# USB_Power_Hub.net
KiCad netlist of a schematic drawn in EAGLE
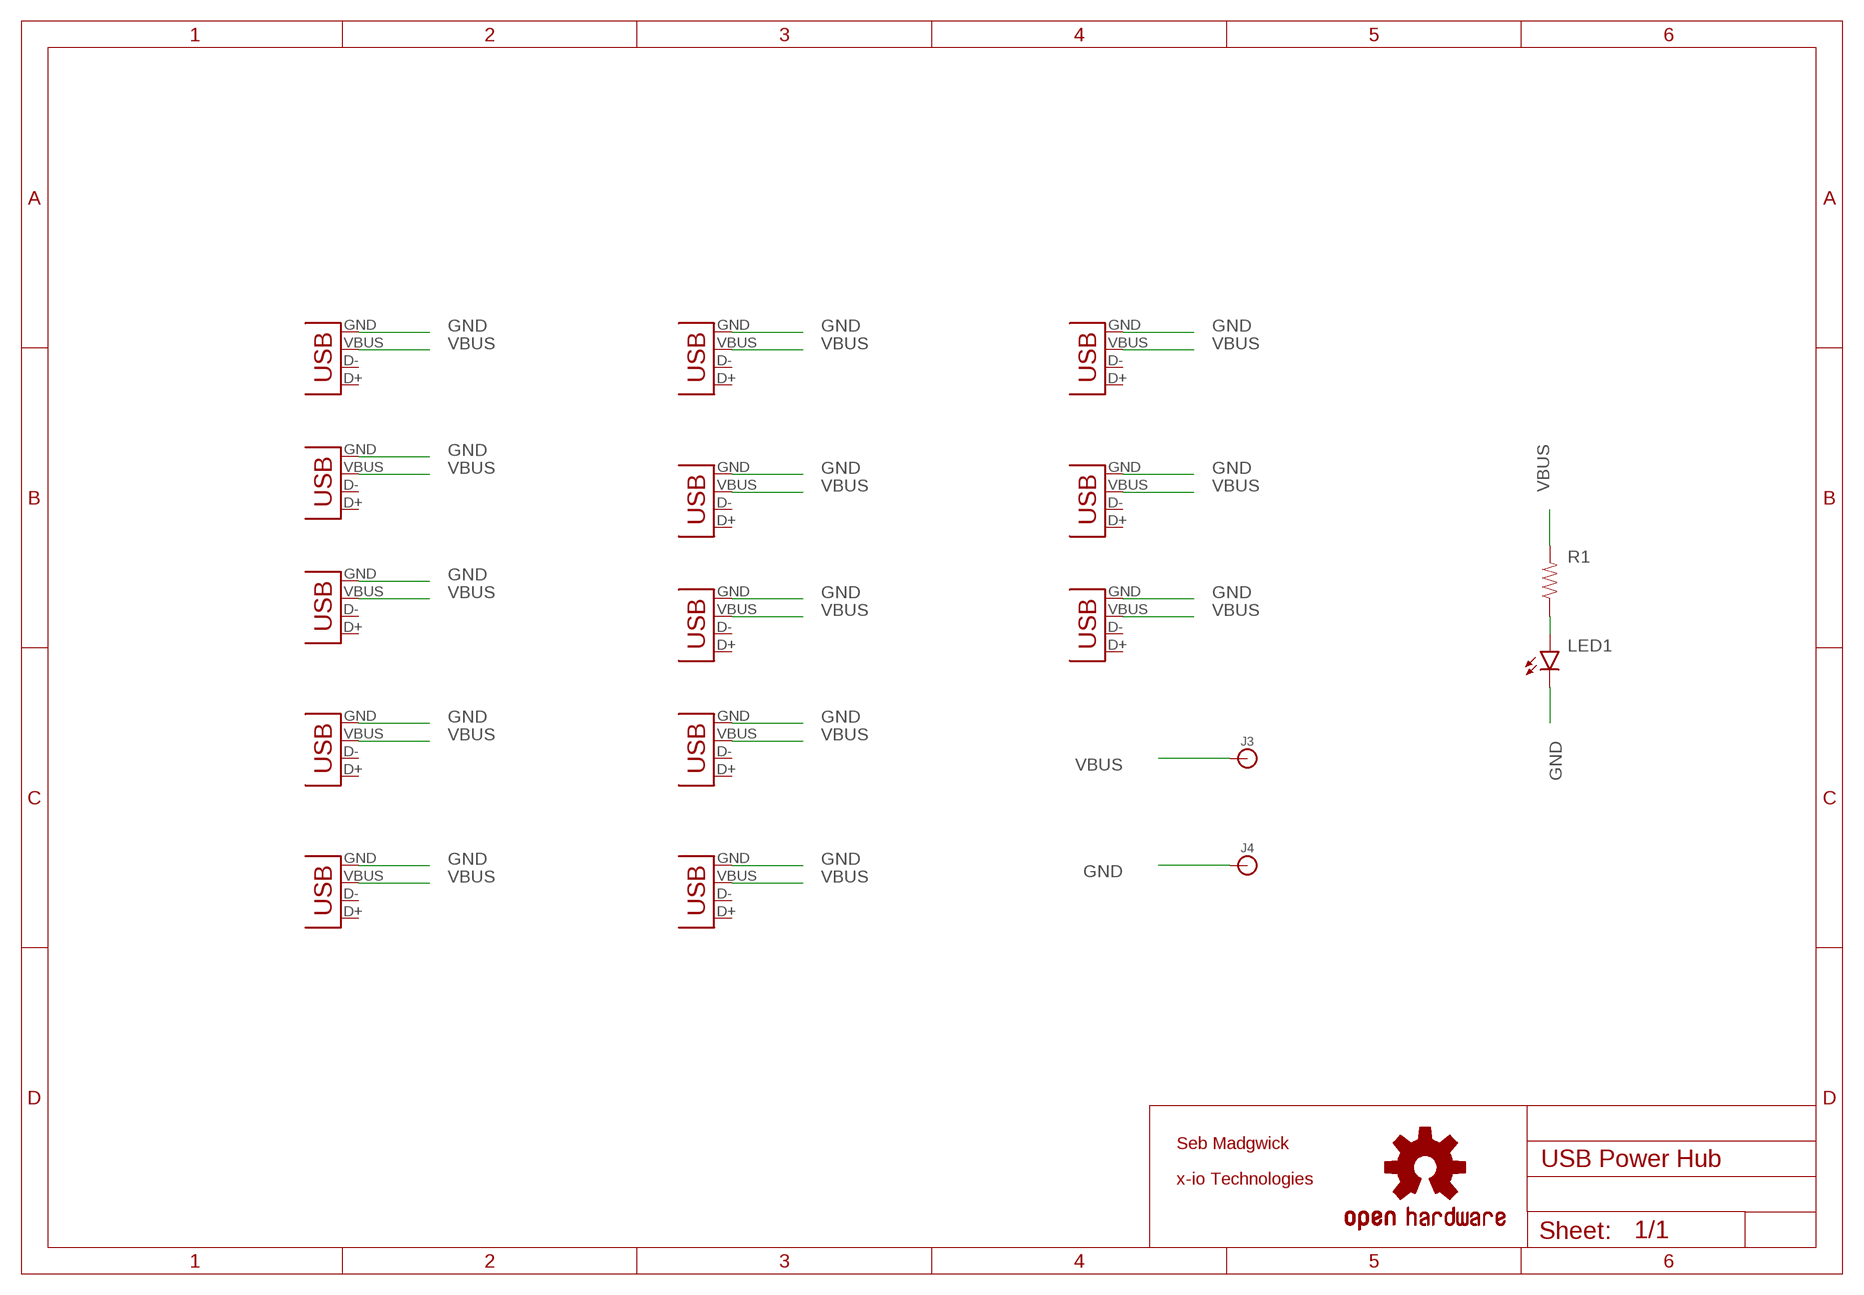
[diagram p0: schematic, sheet 1]

(export (version "E")
  (design (tool "Eeschema 10.0.6"))
  (components
    (comp (ref "J3")
      (value "BANANA_CONN")
      (footprint "eagle-import:BANANA_CONN")
      (libsource (lib "eagle-import") (part "BANANA_CONN"))
    )
    (comp (ref "J4")
      (value "BANANA_CONN")
      (footprint "eagle-import:BANANA_CONN")
      (libsource (lib "eagle-import") (part "BANANA_CONN"))
    )
    (comp (ref "JP1")
      (value "USB-A-S")
      (footprint "eagle-import:USB-A-S")
      (libsource (lib "eagle-import") (part "USB-A-S"))
    )
    (comp (ref "JP2")
      (value "USB-A-S")
      (footprint "eagle-import:USB-A-S")
      (libsource (lib "eagle-import") (part "USB-A-S"))
    )
    (comp (ref "JP3")
      (value "USB-A-S")
      (footprint "eagle-import:USB-A-S")
      (libsource (lib "eagle-import") (part "USB-A-S"))
    )
    (comp (ref "JP4")
      (value "USB-A-S")
      (footprint "eagle-import:USB-A-S")
      (libsource (lib "eagle-import") (part "USB-A-S"))
    )
    (comp (ref "JP5")
      (value "USB-A-S")
      (footprint "eagle-import:USB-A-S")
      (libsource (lib "eagle-import") (part "USB-A-S"))
    )
    (comp (ref "JP6")
      (value "USB-A-S")
      (footprint "eagle-import:USB-A-S")
      (libsource (lib "eagle-import") (part "USB-A-S"))
    )
    (comp (ref "JP7")
      (value "USB-A-S")
      (footprint "eagle-import:USB-A-S")
      (libsource (lib "eagle-import") (part "USB-A-S"))
    )
    (comp (ref "JP8")
      (value "USB-A-S")
      (footprint "eagle-import:USB-A-S")
      (libsource (lib "eagle-import") (part "USB-A-S"))
    )
    (comp (ref "JP9")
      (value "USB-A-S")
      (footprint "eagle-import:USB-A-S")
      (libsource (lib "eagle-import") (part "USB-A-S"))
    )
    (comp (ref "JP10")
      (value "USB-A-S")
      (footprint "eagle-import:USB-A-S")
      (libsource (lib "eagle-import") (part "USB-A-S"))
    )
    (comp (ref "JP11")
      (value "USB-A-S")
      (footprint "eagle-import:USB-A-S")
      (libsource (lib "eagle-import") (part "USB-A-S"))
    )
    (comp (ref "JP12")
      (value "USB-A-S")
      (footprint "eagle-import:USB-A-S")
      (libsource (lib "eagle-import") (part "USB-A-S"))
    )
    (comp (ref "JP13")
      (value "USB-A-S")
      (footprint "eagle-import:USB-A-S")
      (libsource (lib "eagle-import") (part "USB-A-S"))
    )
    (comp (ref "LED1")
      (value "LED5MM")
      (footprint "eagle-import:LED5MM")
      (libsource (lib "eagle-import") (part "LED5MM"))
    )
    (comp (ref "LOGO1")
      (value "OSHW-LOGOL")
      (footprint "eagle-import:OSHW-LOGO-L")
      (libsource (lib "eagle-import") (part "OSHW-LOGOL"))
    )
    (comp (ref "R1")
      (value "RESISTOREZ")
      (footprint "eagle-import:AXIAL-0.3EZ")
      (libsource (lib "eagle-import") (part "RESISTOREZ"))
    )
  )
  (nets
    (net (code "1") (name "/GND") (class "Default")
      (node (ref "J4") (pin "P$1") (pinfunction "1_P$1") (pintype "passive"))
      (node (ref "JP1") (pin "GND") (pinfunction "GND_GND") (pintype "bidirectional"))
      (node (ref "JP10") (pin "GND") (pinfunction "GND_GND") (pintype "bidirectional"))
      (node (ref "JP11") (pin "GND") (pinfunction "GND_GND") (pintype "bidirectional"))
      (node (ref "JP12") (pin "GND") (pinfunction "GND_GND") (pintype "bidirectional"))
      (node (ref "JP13") (pin "GND") (pinfunction "GND_GND") (pintype "bidirectional"))
      (node (ref "JP2") (pin "GND") (pinfunction "GND_GND") (pintype "bidirectional"))
      (node (ref "JP3") (pin "GND") (pinfunction "GND_GND") (pintype "bidirectional"))
      (node (ref "JP4") (pin "GND") (pinfunction "GND_GND") (pintype "bidirectional"))
      (node (ref "JP5") (pin "GND") (pinfunction "GND_GND") (pintype "bidirectional"))
      (node (ref "JP6") (pin "GND") (pinfunction "GND_GND") (pintype "bidirectional"))
      (node (ref "JP7") (pin "GND") (pinfunction "GND_GND") (pintype "bidirectional"))
      (node (ref "JP8") (pin "GND") (pinfunction "GND_GND") (pintype "bidirectional"))
      (node (ref "JP9") (pin "GND") (pinfunction "GND_GND") (pintype "bidirectional"))
      (node (ref "LED1") (pin "K") (pinfunction "C_K") (pintype "passive"))
    )
    (net (code "2") (name "/VBUS") (class "Default")
      (node (ref "J3") (pin "P$1") (pinfunction "1_P$1") (pintype "passive"))
      (node (ref "JP1") (pin "VBUS") (pinfunction "VBUS_VBUS") (pintype "bidirectional"))
      (node (ref "JP10") (pin "VBUS") (pinfunction "VBUS_VBUS") (pintype "bidirectional"))
      (node (ref "JP11") (pin "VBUS") (pinfunction "VBUS_VBUS") (pintype "bidirectional"))
      (node (ref "JP12") (pin "VBUS") (pinfunction "VBUS_VBUS") (pintype "bidirectional"))
      (node (ref "JP13") (pin "VBUS") (pinfunction "VBUS_VBUS") (pintype "bidirectional"))
      (node (ref "JP2") (pin "VBUS") (pinfunction "VBUS_VBUS") (pintype "bidirectional"))
      (node (ref "JP3") (pin "VBUS") (pinfunction "VBUS_VBUS") (pintype "bidirectional"))
      (node (ref "JP4") (pin "VBUS") (pinfunction "VBUS_VBUS") (pintype "bidirectional"))
      (node (ref "JP5") (pin "VBUS") (pinfunction "VBUS_VBUS") (pintype "bidirectional"))
      (node (ref "JP6") (pin "VBUS") (pinfunction "VBUS_VBUS") (pintype "bidirectional"))
      (node (ref "JP7") (pin "VBUS") (pinfunction "VBUS_VBUS") (pintype "bidirectional"))
      (node (ref "JP8") (pin "VBUS") (pinfunction "VBUS_VBUS") (pintype "bidirectional"))
      (node (ref "JP9") (pin "VBUS") (pinfunction "VBUS_VBUS") (pintype "bidirectional"))
      (node (ref "R1") (pin "P$2") (pinfunction "2_P$2") (pintype "passive"))
    )
    (net (code "3") (name "Net-(R1-1)") (class "Default")
      (node (ref "LED1") (pin "A") (pinfunction "A_A") (pintype "passive"))
      (node (ref "R1") (pin "P$1") (pinfunction "1_P$1") (pintype "passive"))
    )
    (net (code "4") (name "unconnected-(JP1-PadD+)") (class "Default")
      (node (ref "JP1") (pin "D+") (pinfunction "D+_D+") (pintype "bidirectional"))
    )
    (net (code "5") (name "unconnected-(JP1-PadD-)") (class "Default")
      (node (ref "JP1") (pin "D-") (pinfunction "D-_D-") (pintype "bidirectional"))
    )
    (net (code "6") (name "unconnected-(JP2-PadD+)") (class "Default")
      (node (ref "JP2") (pin "D+") (pinfunction "D+_D+") (pintype "bidirectional"))
    )
    (net (code "7") (name "unconnected-(JP2-PadD-)") (class "Default")
      (node (ref "JP2") (pin "D-") (pinfunction "D-_D-") (pintype "bidirectional"))
    )
    (net (code "8") (name "unconnected-(JP3-PadD+)") (class "Default")
      (node (ref "JP3") (pin "D+") (pinfunction "D+_D+") (pintype "bidirectional"))
    )
    (net (code "9") (name "unconnected-(JP3-PadD-)") (class "Default")
      (node (ref "JP3") (pin "D-") (pinfunction "D-_D-") (pintype "bidirectional"))
    )
    (net (code "10") (name "unconnected-(JP4-PadD+)") (class "Default")
      (node (ref "JP4") (pin "D+") (pinfunction "D+_D+") (pintype "bidirectional"))
    )
    (net (code "11") (name "unconnected-(JP4-PadD-)") (class "Default")
      (node (ref "JP4") (pin "D-") (pinfunction "D-_D-") (pintype "bidirectional"))
    )
    (net (code "12") (name "unconnected-(JP5-PadD+)") (class "Default")
      (node (ref "JP5") (pin "D+") (pinfunction "D+_D+") (pintype "bidirectional"))
    )
    (net (code "13") (name "unconnected-(JP5-PadD-)") (class "Default")
      (node (ref "JP5") (pin "D-") (pinfunction "D-_D-") (pintype "bidirectional"))
    )
    (net (code "14") (name "unconnected-(JP6-PadD+)") (class "Default")
      (node (ref "JP6") (pin "D+") (pinfunction "D+_D+") (pintype "bidirectional"))
    )
    (net (code "15") (name "unconnected-(JP6-PadD-)") (class "Default")
      (node (ref "JP6") (pin "D-") (pinfunction "D-_D-") (pintype "bidirectional"))
    )
    (net (code "16") (name "unconnected-(JP7-PadD+)") (class "Default")
      (node (ref "JP7") (pin "D+") (pinfunction "D+_D+") (pintype "bidirectional"))
    )
    (net (code "17") (name "unconnected-(JP7-PadD-)") (class "Default")
      (node (ref "JP7") (pin "D-") (pinfunction "D-_D-") (pintype "bidirectional"))
    )
    (net (code "18") (name "unconnected-(JP8-PadD+)") (class "Default")
      (node (ref "JP8") (pin "D+") (pinfunction "D+_D+") (pintype "bidirectional"))
    )
    (net (code "19") (name "unconnected-(JP8-PadD-)") (class "Default")
      (node (ref "JP8") (pin "D-") (pinfunction "D-_D-") (pintype "bidirectional"))
    )
    (net (code "20") (name "unconnected-(JP9-PadD+)") (class "Default")
      (node (ref "JP9") (pin "D+") (pinfunction "D+_D+") (pintype "bidirectional"))
    )
    (net (code "21") (name "unconnected-(JP9-PadD-)") (class "Default")
      (node (ref "JP9") (pin "D-") (pinfunction "D-_D-") (pintype "bidirectional"))
    )
    (net (code "22") (name "unconnected-(JP10-PadD+)") (class "Default")
      (node (ref "JP10") (pin "D+") (pinfunction "D+_D+") (pintype "bidirectional"))
    )
    (net (code "23") (name "unconnected-(JP10-PadD-)") (class "Default")
      (node (ref "JP10") (pin "D-") (pinfunction "D-_D-") (pintype "bidirectional"))
    )
    (net (code "24") (name "unconnected-(JP11-PadD+)") (class "Default")
      (node (ref "JP11") (pin "D+") (pinfunction "D+_D+") (pintype "bidirectional"))
    )
    (net (code "25") (name "unconnected-(JP11-PadD-)") (class "Default")
      (node (ref "JP11") (pin "D-") (pinfunction "D-_D-") (pintype "bidirectional"))
    )
    (net (code "26") (name "unconnected-(JP12-PadD+)") (class "Default")
      (node (ref "JP12") (pin "D+") (pinfunction "D+_D+") (pintype "bidirectional"))
    )
    (net (code "27") (name "unconnected-(JP12-PadD-)") (class "Default")
      (node (ref "JP12") (pin "D-") (pinfunction "D-_D-") (pintype "bidirectional"))
    )
    (net (code "28") (name "unconnected-(JP13-PadD+)") (class "Default")
      (node (ref "JP13") (pin "D+") (pinfunction "D+_D+") (pintype "bidirectional"))
    )
    (net (code "29") (name "unconnected-(JP13-PadD-)") (class "Default")
      (node (ref "JP13") (pin "D-") (pinfunction "D-_D-") (pintype "bidirectional"))
    )
  )
)
